# audio.net
KiCad netlist of a schematic drawn in EAGLE
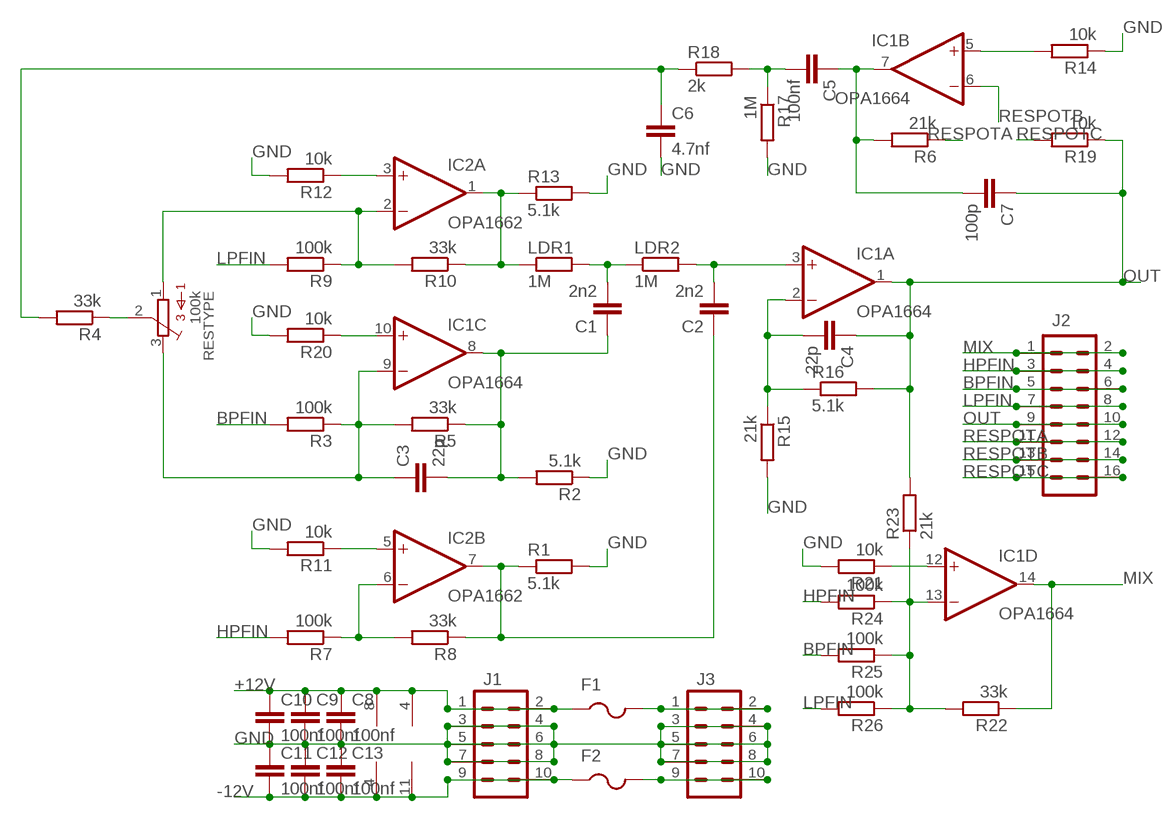
[diagram p0: schematic, sheet 1]

(export (version "E")
  (design (tool "Eeschema 10.0.6"))
  (components
    (comp (ref "C1")
      (value "2n2")
      (footprint "eagle-import:C050-025X075")
      (libsource (lib "eagle-import") (part "C-EU050-025X075"))
    )
    (comp (ref "C2")
      (value "2n2")
      (footprint "eagle-import:C050-025X075")
      (libsource (lib "eagle-import") (part "C-EU050-025X075"))
    )
    (comp (ref "C3")
      (value "22p")
      (footprint "eagle-import:C1206")
      (libsource (lib "eagle-import") (part "C-EUC1206"))
    )
    (comp (ref "C4")
      (value "22p")
      (footprint "eagle-import:C1206")
      (libsource (lib "eagle-import") (part "C-EUC1206"))
    )
    (comp (ref "C5")
      (value "100nf")
      (footprint "eagle-import:C1206")
      (libsource (lib "eagle-import") (part "C-EUC1206"))
    )
    (comp (ref "C6")
      (value "4.7nf")
      (footprint "eagle-import:C1206")
      (libsource (lib "eagle-import") (part "C-EUC1206"))
    )
    (comp (ref "C7")
      (value "100p")
      (footprint "eagle-import:C1206")
      (libsource (lib "eagle-import") (part "C-EUC1206"))
    )
    (comp (ref "C8")
      (value "100nf")
      (footprint "eagle-import:C1206")
      (libsource (lib "eagle-import") (part "C-EUC1206"))
    )
    (comp (ref "C9")
      (value "100nf")
      (footprint "eagle-import:C1206")
      (libsource (lib "eagle-import") (part "C-EUC1206"))
    )
    (comp (ref "C10")
      (value "100nf")
      (footprint "eagle-import:C1206")
      (libsource (lib "eagle-import") (part "C-EUC1206"))
    )
    (comp (ref "C11")
      (value "100nf")
      (footprint "eagle-import:C1206")
      (libsource (lib "eagle-import") (part "C-EUC1206"))
    )
    (comp (ref "C12")
      (value "100nf")
      (footprint "eagle-import:C1206")
      (libsource (lib "eagle-import") (part "C-EUC1206"))
    )
    (comp (ref "C13")
      (value "100nf")
      (footprint "eagle-import:C1206")
      (libsource (lib "eagle-import") (part "C-EUC1206"))
    )
    (comp (ref "F1")
      (value "PTCFUSE-1206")
      (footprint "eagle-import:R1206")
      (libsource (lib "eagle-import") (part "PTCFUSE-1206"))
    )
    (comp (ref "F2")
      (value "PTCFUSE-1206")
      (footprint "eagle-import:R1206")
      (libsource (lib "eagle-import") (part "PTCFUSE-1206"))
    )
    (comp (ref "IC1")
      (value "OPA1664")
      (footprint "eagle-import:SO14")
      (libsource (lib "eagle-import") (part "TL074D"))
    )
    (comp (ref "IC2")
      (value "OPA1662")
      (footprint "eagle-import:SO08")
      (libsource (lib "eagle-import") (part "TL072D"))
    )
    (comp (ref "J1")
      (value "M05X2PTH")
      (footprint "eagle-import:AVR_ICSP")
      (libsource (lib "eagle-import") (part "M05X2PTH"))
    )
    (comp (ref "J2")
      (value "M08X2")
      (footprint "eagle-import:2X8")
      (libsource (lib "eagle-import") (part "M08X2"))
    )
    (comp (ref "J3")
      (value "M05X2PTH")
      (footprint "eagle-import:AVR_ICSP")
      (libsource (lib "eagle-import") (part "M05X2PTH"))
    )
    (comp (ref "LDR1")
      (value "1M")
      (footprint "eagle-import:0411V")
      (libsource (lib "eagle-import") (part "R-EU_0411/3V"))
    )
    (comp (ref "LDR2")
      (value "1M")
      (footprint "eagle-import:0411V")
      (libsource (lib "eagle-import") (part "R-EU_0411/3V"))
    )
    (comp (ref "R1")
      (value "5.1k")
      (footprint "eagle-import:R1206")
      (libsource (lib "eagle-import") (part "R-EU_R1206"))
    )
    (comp (ref "R2")
      (value "5.1k")
      (footprint "eagle-import:R1206")
      (libsource (lib "eagle-import") (part "R-EU_R1206"))
    )
    (comp (ref "R3")
      (value "100k")
      (footprint "eagle-import:R1206")
      (libsource (lib "eagle-import") (part "R-EU_R1206"))
    )
    (comp (ref "R4")
      (value "33k")
      (footprint "eagle-import:R1206")
      (libsource (lib "eagle-import") (part "R-EU_R1206"))
    )
    (comp (ref "R5")
      (value "33k")
      (footprint "eagle-import:R1206")
      (libsource (lib "eagle-import") (part "R-EU_R1206"))
    )
    (comp (ref "R6")
      (value "21k")
      (footprint "eagle-import:R1206")
      (libsource (lib "eagle-import") (part "R-EU_R1206"))
    )
    (comp (ref "R7")
      (value "100k")
      (footprint "eagle-import:R1206")
      (libsource (lib "eagle-import") (part "R-EU_R1206"))
    )
    (comp (ref "R8")
      (value "33k")
      (footprint "eagle-import:R1206")
      (libsource (lib "eagle-import") (part "R-EU_R1206"))
    )
    (comp (ref "R9")
      (value "100k")
      (footprint "eagle-import:R1206")
      (libsource (lib "eagle-import") (part "R-EU_R1206"))
    )
    (comp (ref "R10")
      (value "33k")
      (footprint "eagle-import:R1206")
      (libsource (lib "eagle-import") (part "R-EU_R1206"))
    )
    (comp (ref "R11")
      (value "10k")
      (footprint "eagle-import:R1206")
      (libsource (lib "eagle-import") (part "R-EU_R1206"))
    )
    (comp (ref "R12")
      (value "10k")
      (footprint "eagle-import:R1206")
      (libsource (lib "eagle-import") (part "R-EU_R1206"))
    )
    (comp (ref "R13")
      (value "5.1k")
      (footprint "eagle-import:R1206")
      (libsource (lib "eagle-import") (part "R-EU_R1206"))
    )
    (comp (ref "R14")
      (value "10k")
      (footprint "eagle-import:R1206")
      (libsource (lib "eagle-import") (part "R-EU_R1206"))
    )
    (comp (ref "R15")
      (value "21k")
      (footprint "eagle-import:R1206")
      (libsource (lib "eagle-import") (part "R-EU_R1206"))
    )
    (comp (ref "R16")
      (value "5.1k")
      (footprint "eagle-import:R1206")
      (libsource (lib "eagle-import") (part "R-EU_R1206"))
    )
    (comp (ref "R17")
      (value "1M")
      (footprint "eagle-import:R1206")
      (libsource (lib "eagle-import") (part "R-EU_R1206"))
    )
    (comp (ref "R18")
      (value "2k")
      (footprint "eagle-import:R1206")
      (libsource (lib "eagle-import") (part "R-EU_R1206"))
    )
    (comp (ref "R19")
      (value "10k")
      (footprint "eagle-import:R1206")
      (libsource (lib "eagle-import") (part "R-EU_R1206"))
    )
    (comp (ref "R20")
      (value "10k")
      (footprint "eagle-import:R1206")
      (libsource (lib "eagle-import") (part "R-EU_R1206"))
    )
    (comp (ref "R21")
      (value "10k")
      (footprint "eagle-import:R1206")
      (libsource (lib "eagle-import") (part "R-EU_R1206"))
    )
    (comp (ref "R22")
      (value "33k")
      (footprint "eagle-import:R1206")
      (libsource (lib "eagle-import") (part "R-EU_R1206"))
    )
    (comp (ref "R23")
      (value "21k")
      (footprint "eagle-import:R1206")
      (libsource (lib "eagle-import") (part "R-EU_R1206"))
    )
    (comp (ref "R24")
      (value "100k")
      (footprint "eagle-import:R1206")
      (libsource (lib "eagle-import") (part "R-EU_R1206"))
    )
    (comp (ref "R25")
      (value "100k")
      (footprint "eagle-import:R1206")
      (libsource (lib "eagle-import") (part "R-EU_R1206"))
    )
    (comp (ref "R26")
      (value "100k")
      (footprint "eagle-import:R1206")
      (libsource (lib "eagle-import") (part "R-EU_R1206"))
    )
    (comp (ref "RESTYPE")
      (value "100k")
      (footprint "eagle-import:3386C")
      (libsource (lib "eagle-import") (part "3386-C"))
    )
  )
  (nets
    (net (code "1") (name "/+12V") (class "Default")
      (node (ref "C10") (pin "1") (pinfunction "1_1") (pintype "passive"))
      (node (ref "C8") (pin "1") (pinfunction "1_1") (pintype "passive"))
      (node (ref "C9") (pin "1") (pinfunction "1_1") (pintype "passive"))
      (node (ref "F1") (pin "1") (pinfunction "1_1") (pintype "passive"))
      (node (ref "IC1") (pin "4") (pinfunction "V+_4") (pintype "power_in"))
      (node (ref "IC2") (pin "8") (pinfunction "V+_8") (pintype "power_in"))
      (node (ref "J1") (pin "1") (pinfunction "1_1") (pintype "passive"))
      (node (ref "J1") (pin "2") (pinfunction "2_2") (pintype "passive"))
    )
    (net (code "2") (name "/-12V") (class "Default")
      (node (ref "C11") (pin "2") (pinfunction "2_2") (pintype "passive"))
      (node (ref "C12") (pin "2") (pinfunction "2_2") (pintype "passive"))
      (node (ref "C13") (pin "2") (pinfunction "2_2") (pintype "passive"))
      (node (ref "F2") (pin "1") (pinfunction "1_1") (pintype "passive"))
      (node (ref "IC1") (pin "11") (pinfunction "V-_11") (pintype "power_in"))
      (node (ref "IC2") (pin "4") (pinfunction "V-_4") (pintype "power_in"))
      (node (ref "J1") (pin "10") (pinfunction "10_10") (pintype "passive"))
      (node (ref "J1") (pin "9") (pinfunction "9_9") (pintype "passive"))
    )
    (net (code "3") (name "/BPFIN") (class "Default")
      (node (ref "J2") (pin "5") (pinfunction "5_5") (pintype "passive"))
      (node (ref "J2") (pin "6") (pinfunction "6_6") (pintype "passive"))
      (node (ref "R25") (pin "2") (pinfunction "2_2") (pintype "passive"))
      (node (ref "R3") (pin "2") (pinfunction "2_2") (pintype "passive"))
    )
    (net (code "4") (name "/GND") (class "Default")
      (node (ref "C10") (pin "2") (pinfunction "2_2") (pintype "passive"))
      (node (ref "C11") (pin "1") (pinfunction "1_1") (pintype "passive"))
      (node (ref "C12") (pin "1") (pinfunction "1_1") (pintype "passive"))
      (node (ref "C13") (pin "1") (pinfunction "1_1") (pintype "passive"))
      (node (ref "C6") (pin "2") (pinfunction "2_2") (pintype "passive"))
      (node (ref "C8") (pin "2") (pinfunction "2_2") (pintype "passive"))
      (node (ref "C9") (pin "2") (pinfunction "2_2") (pintype "passive"))
      (node (ref "J1") (pin "3") (pinfunction "3_3") (pintype "passive"))
      (node (ref "J1") (pin "4") (pinfunction "4_4") (pintype "passive"))
      (node (ref "J1") (pin "5") (pinfunction "5_5") (pintype "passive"))
      (node (ref "J1") (pin "6") (pinfunction "6_6") (pintype "passive"))
      (node (ref "J1") (pin "7") (pinfunction "7_7") (pintype "passive"))
      (node (ref "J1") (pin "8") (pinfunction "8_8") (pintype "passive"))
      (node (ref "J3") (pin "3") (pinfunction "3_3") (pintype "passive"))
      (node (ref "J3") (pin "4") (pinfunction "4_4") (pintype "passive"))
      (node (ref "J3") (pin "5") (pinfunction "5_5") (pintype "passive"))
      (node (ref "J3") (pin "6") (pinfunction "6_6") (pintype "passive"))
      (node (ref "J3") (pin "7") (pinfunction "7_7") (pintype "passive"))
      (node (ref "J3") (pin "8") (pinfunction "8_8") (pintype "passive"))
      (node (ref "R1") (pin "2") (pinfunction "2_2") (pintype "passive"))
      (node (ref "R11") (pin "2") (pinfunction "2_2") (pintype "passive"))
      (node (ref "R12") (pin "2") (pinfunction "2_2") (pintype "passive"))
      (node (ref "R13") (pin "2") (pinfunction "2_2") (pintype "passive"))
      (node (ref "R14") (pin "1") (pinfunction "1_1") (pintype "passive"))
      (node (ref "R15") (pin "2") (pinfunction "2_2") (pintype "passive"))
      (node (ref "R17") (pin "2") (pinfunction "2_2") (pintype "passive"))
      (node (ref "R2") (pin "1") (pinfunction "1_1") (pintype "passive"))
      (node (ref "R20") (pin "2") (pinfunction "2_2") (pintype "passive"))
      (node (ref "R21") (pin "2") (pinfunction "2_2") (pintype "passive"))
    )
    (net (code "5") (name "/HPFIN") (class "Default")
      (node (ref "J2") (pin "3") (pinfunction "3_3") (pintype "passive"))
      (node (ref "J2") (pin "4") (pinfunction "4_4") (pintype "passive"))
      (node (ref "R24") (pin "2") (pinfunction "2_2") (pintype "passive"))
      (node (ref "R7") (pin "2") (pinfunction "2_2") (pintype "passive"))
    )
    (net (code "6") (name "/LPFIN") (class "Default")
      (node (ref "J2") (pin "7") (pinfunction "7_7") (pintype "passive"))
      (node (ref "J2") (pin "8") (pinfunction "8_8") (pintype "passive"))
      (node (ref "R26") (pin "2") (pinfunction "2_2") (pintype "passive"))
      (node (ref "R9") (pin "2") (pinfunction "2_2") (pintype "passive"))
    )
    (net (code "7") (name "/MIX") (class "Default")
      (node (ref "IC1") (pin "14") (pinfunction "OUT_14") (pintype "output"))
      (node (ref "J2") (pin "1") (pinfunction "1_1") (pintype "passive"))
      (node (ref "J2") (pin "2") (pinfunction "2_2") (pintype "passive"))
      (node (ref "R22") (pin "1") (pinfunction "1_1") (pintype "passive"))
    )
    (net (code "8") (name "/OUT") (class "Default")
      (node (ref "C4") (pin "1") (pinfunction "1_1") (pintype "passive"))
      (node (ref "C7") (pin "1") (pinfunction "1_1") (pintype "passive"))
      (node (ref "IC1") (pin "1") (pinfunction "OUT_1") (pintype "output"))
      (node (ref "J2") (pin "10") (pinfunction "10_10") (pintype "passive"))
      (node (ref "J2") (pin "9") (pinfunction "9_9") (pintype "passive"))
      (node (ref "R16") (pin "2") (pinfunction "2_2") (pintype "passive"))
      (node (ref "R19") (pin "1") (pinfunction "1_1") (pintype "passive"))
      (node (ref "R23") (pin "2") (pinfunction "2_2") (pintype "passive"))
    )
    (net (code "9") (name "/RESPOTA") (class "Default")
      (node (ref "J2") (pin "11") (pinfunction "11_11") (pintype "passive"))
      (node (ref "J2") (pin "12") (pinfunction "12_12") (pintype "passive"))
      (node (ref "R6") (pin "1") (pinfunction "1_1") (pintype "passive"))
    )
    (net (code "10") (name "/RESPOTB") (class "Default")
      (node (ref "IC1") (pin "6") (pinfunction "-IN_6") (pintype "input"))
      (node (ref "J2") (pin "13") (pinfunction "13_13") (pintype "passive"))
      (node (ref "J2") (pin "14") (pinfunction "14_14") (pintype "passive"))
    )
    (net (code "11") (name "/RESPOTC") (class "Default")
      (node (ref "J2") (pin "15") (pinfunction "15_15") (pintype "passive"))
      (node (ref "J2") (pin "16") (pinfunction "16_16") (pintype "passive"))
      (node (ref "R19") (pin "2") (pinfunction "2_2") (pintype "passive"))
    )
    (net (code "12") (name "Net-(C1-Pad2)") (class "Default")
      (node (ref "C1") (pin "2") (pinfunction "2_2") (pintype "passive"))
      (node (ref "LDR1") (pin "2") (pinfunction "2_2") (pintype "passive"))
      (node (ref "LDR2") (pin "1") (pinfunction "1_1") (pintype "passive"))
    )
    (net (code "13") (name "Net-(C5-Pad2)") (class "Default")
      (node (ref "C5") (pin "2") (pinfunction "2_2") (pintype "passive"))
      (node (ref "R17") (pin "1") (pinfunction "1_1") (pintype "passive"))
      (node (ref "R18") (pin "2") (pinfunction "2_2") (pintype "passive"))
    )
    (net (code "14") (name "Net-(C6-Pad1)") (class "Default")
      (node (ref "C6") (pin "1") (pinfunction "1_1") (pintype "passive"))
      (node (ref "R18") (pin "1") (pinfunction "1_1") (pintype "passive"))
      (node (ref "R4") (pin "2") (pinfunction "2_2") (pintype "passive"))
    )
    (net (code "15") (name "Net-(F1-Pad2)") (class "Default")
      (node (ref "F1") (pin "2") (pinfunction "2_2") (pintype "passive"))
      (node (ref "J3") (pin "1") (pinfunction "1_1") (pintype "passive"))
      (node (ref "J3") (pin "2") (pinfunction "2_2") (pintype "passive"))
    )
    (net (code "16") (name "Net-(F2-Pad2)") (class "Default")
      (node (ref "F2") (pin "2") (pinfunction "2_2") (pintype "passive"))
      (node (ref "J3") (pin "10") (pinfunction "10_10") (pintype "passive"))
      (node (ref "J3") (pin "9") (pinfunction "9_9") (pintype "passive"))
    )
    (net (code "17") (name "Net-(IC1A-+IN)") (class "Default")
      (node (ref "C2") (pin "2") (pinfunction "2_2") (pintype "passive"))
      (node (ref "IC1") (pin "3") (pinfunction "+IN_3") (pintype "input"))
      (node (ref "LDR2") (pin "2") (pinfunction "2_2") (pintype "passive"))
    )
    (net (code "18") (name "Net-(IC1A--IN)") (class "Default")
      (node (ref "C4") (pin "2") (pinfunction "2_2") (pintype "passive"))
      (node (ref "IC1") (pin "2") (pinfunction "-IN_2") (pintype "input"))
      (node (ref "R15") (pin "1") (pinfunction "1_1") (pintype "passive"))
      (node (ref "R16") (pin "1") (pinfunction "1_1") (pintype "passive"))
    )
    (net (code "19") (name "Net-(IC1B-+IN)") (class "Default")
      (node (ref "IC1") (pin "5") (pinfunction "+IN_5") (pintype "input"))
      (node (ref "R14") (pin "2") (pinfunction "2_2") (pintype "passive"))
    )
    (net (code "20") (name "Net-(IC1B-OUT)") (class "Default")
      (node (ref "C5") (pin "1") (pinfunction "1_1") (pintype "passive"))
      (node (ref "C7") (pin "2") (pinfunction "2_2") (pintype "passive"))
      (node (ref "IC1") (pin "7") (pinfunction "OUT_7") (pintype "output"))
      (node (ref "R6") (pin "2") (pinfunction "2_2") (pintype "passive"))
    )
    (net (code "21") (name "Net-(IC1C-+IN)") (class "Default")
      (node (ref "IC1") (pin "10") (pinfunction "+IN_10") (pintype "input"))
      (node (ref "R20") (pin "1") (pinfunction "1_1") (pintype "passive"))
    )
    (net (code "22") (name "Net-(IC1C--IN)") (class "Default")
      (node (ref "C3") (pin "1") (pinfunction "1_1") (pintype "passive"))
      (node (ref "IC1") (pin "9") (pinfunction "-IN_9") (pintype "input"))
      (node (ref "R3") (pin "1") (pinfunction "1_1") (pintype "passive"))
      (node (ref "R5") (pin "2") (pinfunction "2_2") (pintype "passive"))
      (node (ref "RESTYPE") (pin "3") (pinfunction "3_3") (pintype "passive"))
    )
    (net (code "23") (name "Net-(IC1C-OUT)") (class "Default")
      (node (ref "C1") (pin "1") (pinfunction "1_1") (pintype "passive"))
      (node (ref "C3") (pin "2") (pinfunction "2_2") (pintype "passive"))
      (node (ref "IC1") (pin "8") (pinfunction "OUT_8") (pintype "output"))
      (node (ref "R2") (pin "2") (pinfunction "2_2") (pintype "passive"))
      (node (ref "R5") (pin "1") (pinfunction "1_1") (pintype "passive"))
    )
    (net (code "24") (name "Net-(IC1D-+IN)") (class "Default")
      (node (ref "IC1") (pin "12") (pinfunction "+IN_12") (pintype "input"))
      (node (ref "R21") (pin "1") (pinfunction "1_1") (pintype "passive"))
    )
    (net (code "25") (name "Net-(IC1D--IN)") (class "Default")
      (node (ref "IC1") (pin "13") (pinfunction "-IN_13") (pintype "input"))
      (node (ref "R22") (pin "2") (pinfunction "2_2") (pintype "passive"))
      (node (ref "R23") (pin "1") (pinfunction "1_1") (pintype "passive"))
      (node (ref "R24") (pin "1") (pinfunction "1_1") (pintype "passive"))
      (node (ref "R25") (pin "1") (pinfunction "1_1") (pintype "passive"))
      (node (ref "R26") (pin "1") (pinfunction "1_1") (pintype "passive"))
    )
    (net (code "26") (name "Net-(IC2A-+IN)") (class "Default")
      (node (ref "IC2") (pin "3") (pinfunction "+IN_3") (pintype "input"))
      (node (ref "R12") (pin "1") (pinfunction "1_1") (pintype "passive"))
    )
    (net (code "27") (name "Net-(IC2A--IN)") (class "Default")
      (node (ref "IC2") (pin "2") (pinfunction "-IN_2") (pintype "input"))
      (node (ref "R10") (pin "2") (pinfunction "2_2") (pintype "passive"))
      (node (ref "R9") (pin "1") (pinfunction "1_1") (pintype "passive"))
      (node (ref "RESTYPE") (pin "1") (pinfunction "1_1") (pintype "passive"))
    )
    (net (code "28") (name "Net-(IC2A-OUT)") (class "Default")
      (node (ref "IC2") (pin "1") (pinfunction "OUT_1") (pintype "output"))
      (node (ref "LDR1") (pin "1") (pinfunction "1_1") (pintype "passive"))
      (node (ref "R10") (pin "1") (pinfunction "1_1") (pintype "passive"))
      (node (ref "R13") (pin "1") (pinfunction "1_1") (pintype "passive"))
    )
    (net (code "29") (name "Net-(IC2B-+IN)") (class "Default")
      (node (ref "IC2") (pin "5") (pinfunction "+IN_5") (pintype "input"))
      (node (ref "R11") (pin "1") (pinfunction "1_1") (pintype "passive"))
    )
    (net (code "30") (name "Net-(IC2B--IN)") (class "Default")
      (node (ref "IC2") (pin "6") (pinfunction "-IN_6") (pintype "input"))
      (node (ref "R7") (pin "1") (pinfunction "1_1") (pintype "passive"))
      (node (ref "R8") (pin "2") (pinfunction "2_2") (pintype "passive"))
    )
    (net (code "31") (name "Net-(IC2B-OUT)") (class "Default")
      (node (ref "C2") (pin "1") (pinfunction "1_1") (pintype "passive"))
      (node (ref "IC2") (pin "7") (pinfunction "OUT_7") (pintype "output"))
      (node (ref "R1") (pin "1") (pinfunction "1_1") (pintype "passive"))
      (node (ref "R8") (pin "1") (pinfunction "1_1") (pintype "passive"))
    )
    (net (code "32") (name "Net-(R4-Pad1)") (class "Default")
      (node (ref "R4") (pin "1") (pinfunction "1_1") (pintype "passive"))
      (node (ref "RESTYPE") (pin "2") (pinfunction "2_2") (pintype "passive"))
    )
  )
)
